# Sheet1.net
KiCad netlist of a schematic drawn in Altium Designer
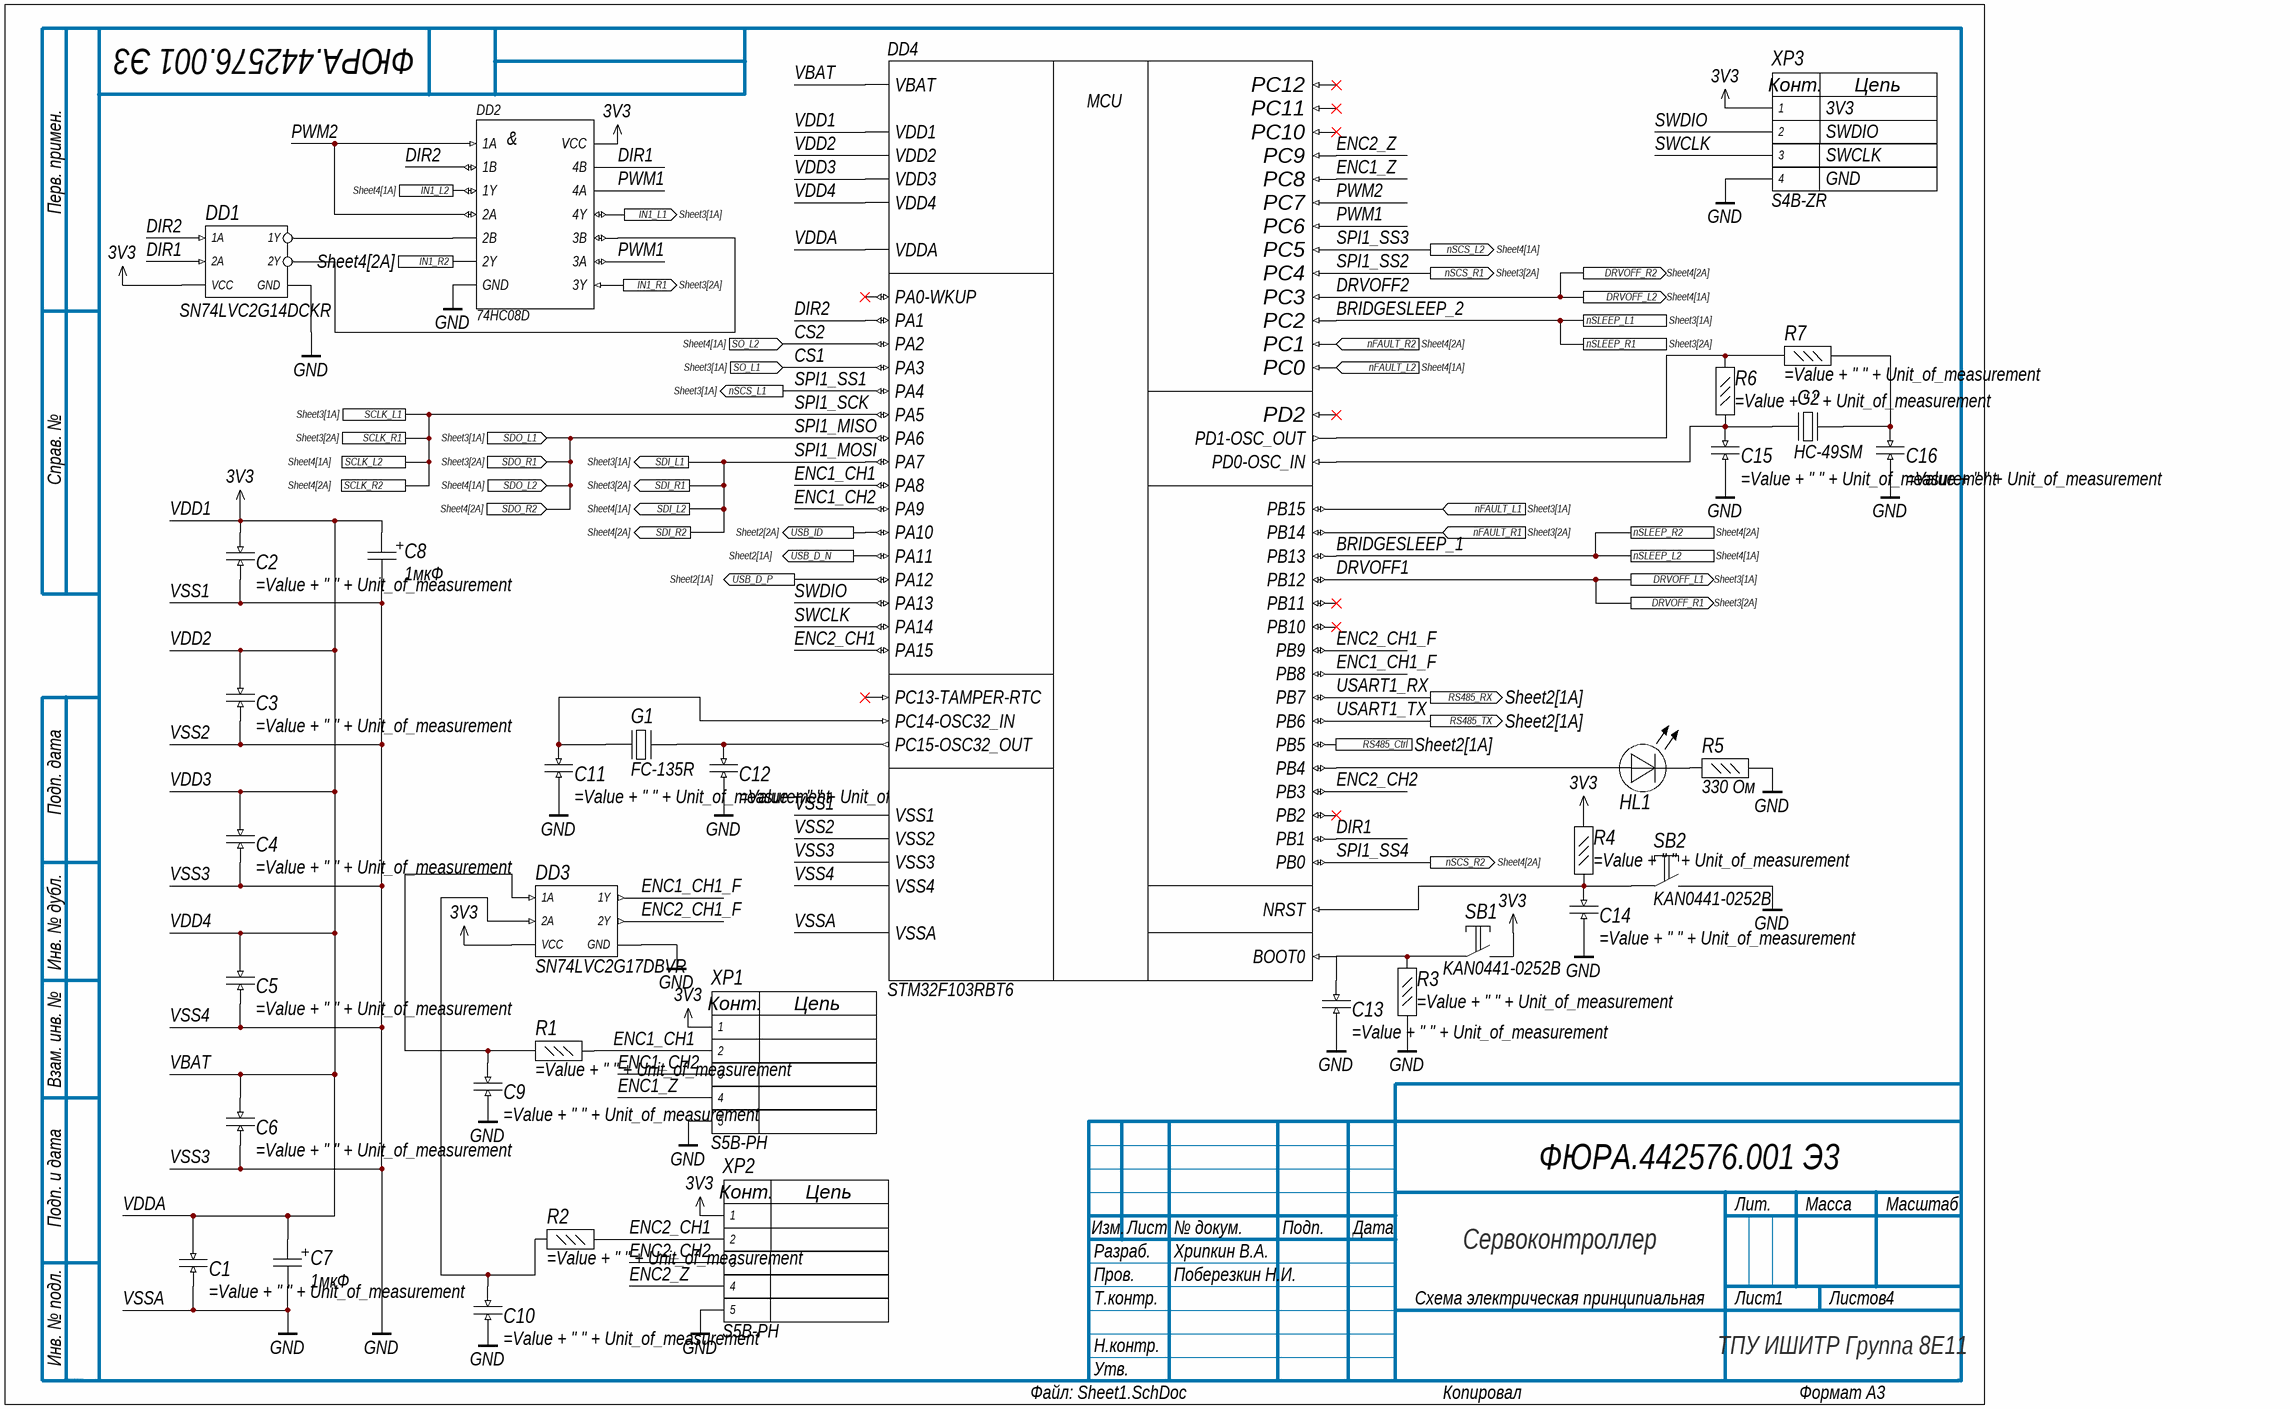
[diagram p0: Sheet1.SchDoc]

(export (version "E")
  (design (tool "Eeschema 10.0.6"))
  (components
    (comp (ref "C1")
      (value "100нФ")
      (footprint "CAP_0603")
      (description "Конденсатор керамический, типоразмера 0603")
      (libsource (lib "PassiveComponents") (part "CAP_0603"))
    )
    (comp (ref "C2")
      (value "100нФ")
      (footprint "CAP_0603")
      (description "Конденсатор керамический, типоразмера 0603")
      (libsource (lib "PassiveComponents") (part "CAP_0603"))
    )
    (comp (ref "C3")
      (value "100нФ")
      (footprint "CAP_0603")
      (description "Конденсатор керамический, типоразмера 0603")
      (libsource (lib "PassiveComponents") (part "CAP_0603"))
    )
    (comp (ref "C4")
      (value "100нФ")
      (footprint "CAP_0603")
      (description "Конденсатор керамический, типоразмера 0603")
      (libsource (lib "PassiveComponents") (part "CAP_0603"))
    )
    (comp (ref "C5")
      (value "100нФ")
      (footprint "CAP_0603")
      (description "Конденсатор керамический, типоразмера 0603")
      (libsource (lib "PassiveComponents") (part "CAP_0603"))
    )
    (comp (ref "C6")
      (value "100нФ")
      (footprint "CAP_0603")
      (description "Конденсатор керамический, типоразмера 0603")
      (libsource (lib "PassiveComponents") (part "CAP_0603"))
    )
    (comp (ref "C7")
      (value "1мкФ")
      (footprint "TECAP_A")
      (description "Описание свойств компонента")
      (libsource (lib "PassiveComponents") (part "TECAP_A"))
    )
    (comp (ref "C8")
      (value "1мкФ")
      (footprint "TECAP_A")
      (description "Описание свойств компонента")
      (libsource (lib "PassiveComponents") (part "TECAP_A"))
    )
    (comp (ref "C9")
      (value "10пФ")
      (footprint "CAP_0603")
      (description "Конденсатор керамический, типоразмера 0603")
      (libsource (lib "PassiveComponents") (part "CAP_0603"))
    )
    (comp (ref "C10")
      (value "10пФ")
      (footprint "CAP_0603")
      (description "Конденсатор керамический, типоразмера 0603")
      (libsource (lib "PassiveComponents") (part "CAP_0603"))
    )
    (comp (ref "C11")
      (value "20пФ")
      (footprint "CAP_0603")
      (description "Конденсатор керамический, типоразмера 0603")
      (libsource (lib "PassiveComponents") (part "CAP_0603"))
    )
    (comp (ref "C12")
      (value "20пФ")
      (footprint "CAP_0603")
      (description "Конденсатор керамический, типоразмера 0603")
      (libsource (lib "PassiveComponents") (part "CAP_0603"))
    )
    (comp (ref "C13")
      (value "100нФ")
      (footprint "CAP_0603")
      (description "Конденсатор керамический, типоразмера 0603")
      (libsource (lib "PassiveComponents") (part "CAP_0603"))
    )
    (comp (ref "C14")
      (value "100нФ")
      (footprint "CAP_0603")
      (description "Конденсатор керамический, типоразмера 0603")
      (libsource (lib "PassiveComponents") (part "CAP_0603"))
    )
    (comp (ref "C15")
      (value "20пФ")
      (footprint "CAP_0603")
      (description "Конденсатор керамический, типоразмера 0603")
      (libsource (lib "PassiveComponents") (part "CAP_0603"))
    )
    (comp (ref "C16")
      (value "20пФ")
      (footprint "CAP_0603")
      (description "Конденсатор керамический, типоразмера 0603")
      (libsource (lib "PassiveComponents") (part "CAP_0603"))
    )
    (comp (ref "DD1")
      (value "SN74LVC2G14DCKR")
      (footprint "SOT363 (SC70-6)")
      (description "Сдвоенный инвертор с триггером Шмидта")
      (libsource (lib "ICs") (part "SN74LVC2G14DCKR"))
    )
    (comp (ref "DD2")
      (value "74HC08D")
      (footprint "SO14")
      (description "Логическая ИС, QUAD 2-INPUT AND GATE")
      (libsource (lib "ICs") (part "74HC08D"))
    )
    (comp (ref "DD3")
      (value "SN74LVC2G17DBVR")
      (footprint "SOT23-6")
      (description "Сдвоенный буфер с триггером Шмитта на входе")
      (libsource (lib "ICs") (part "SN74LVC2G17DBVR"))
    )
    (comp (ref "DD4")
      (value "STM32F103RBT6")
      (footprint "LQFP-64")
      (description "Микроконтроллер 32-Бит, Cortex-M3, 72МГц, 128КБ Flash, USB, CAN [LQFP-64]")
      (libsource (lib "ICs") (part "STM32F103RBT6"))
    )
    (comp (ref "G1")
      (value "FC-135R")
      (footprint "FC-135R")
      (description "Кварцевый резонатор 32,768 кГц; SMD")
      (libsource (lib "Complicated") (part "FC-135R"))
    )
    (comp (ref "G2")
      (value "HC-49SM")
      (footprint "HC-49SM")
      (description "Кварцевый резонатор 8 МГц; SMD")
      (libsource (lib "Complicated") (part "HC-49SM"))
    )
    (comp (ref "HL1") (value "3") (footprint "LED_0805") (libsource (lib "Complicated") (part "LED_0805_O")))
    (comp (ref "R1")
      (value "100кОм")
      (footprint "RES_0603")
      (description "Резистор, типоразмера 0603")
      (libsource (lib "") (part "RES_0603_1"))
    )
    (comp (ref "R2")
      (value "100кОм")
      (footprint "RES_0603")
      (description "Резистор, типоразмера 0603")
      (libsource (lib "") (part "RES_0603_1"))
    )
    (comp (ref "R3")
      (value "10кОм")
      (footprint "RES_0603")
      (description "Резистор, типоразмера 0603")
      (libsource (lib "SimpleComponents") (part "RES_0603"))
    )
    (comp (ref "R4")
      (value "10кОм")
      (footprint "RES_0603")
      (description "Резистор, типоразмера 0603")
      (libsource (lib "") (part "RES_0603_2"))
    )
    (comp (ref "R5")
      (value "330 Ом")
      (footprint "RES_0603")
      (description "Резистор, типоразмера 0603")
      (libsource (lib "") (part "RES_0603_1"))
    )
    (comp (ref "R6")
      (value "1МОм")
      (footprint "RES_0603")
      (description "Резистор, типоразмера 0603")
      (libsource (lib "") (part "RES_0603_2"))
    )
    (comp (ref "R7")
      (value "100кОм")
      (footprint "RES_0603")
      (description "Резистор, типоразмера 0603")
      (libsource (lib "") (part "RES_0603_1"))
    )
    (comp (ref "SB1")
      (value "KAN0441-0252B")
      (footprint "SMD-BUTTON_6x3.5")
      (description "Описание свойств компонента")
      (libsource (lib "PassiveComponents") (part "SMD-Button_6x3.5"))
    )
    (comp (ref "SB2")
      (value "KAN0441-0252B")
      (footprint "SMD-BUTTON_6x3.5")
      (description "Описание свойств компонента")
      (libsource (lib "PassiveComponents") (part "SMD-Button_6x3.5"))
    )
    (comp (ref "XP1")
      (value "S5B-PH")
      (footprint "S5B-PH-K-S")
      (description "JST PH 5pin 2 mm pitch; horizontal; through hole OR full smd; S5B-PH-SM4-TB")
      (libsource (lib "SimpleComponents") (part "S5B-PH"))
    )
    (comp (ref "XP2")
      (value "S5B-PH")
      (footprint "S5B-PH-K-S")
      (description "JST PH 5pin 2 mm pitch; horizontal; through hole OR full smd; S5B-PH-SM4-TB")
      (libsource (lib "SimpleComponents") (part "S5B-PH"))
    )
    (comp (ref "XP3")
      (value "S4B-ZR")
      (footprint "S4B-ZR-SM4A-TF")
      (description "JST ZH 4pin 1.5 mm pitch; horizontal; through hole OR full smd; S4B-ZR")
      (libsource (lib "PassiveComponents") (part "S4B-ZR"))
    )
  )
  (nets
    (net (code "1") (name "/BRIDGESLEEP_1") (class "Default")
      (node (ref "DD4") (pin "34") (pinfunction "PB13_34") (pintype "bidirectional"))
    )
    (net (code "2") (name "/BRIDGESLEEP_2") (class "Default")
      (node (ref "DD4") (pin "10") (pinfunction "PC2_10") (pintype "input"))
    )
    (net (code "3") (name "/CS1") (class "Default")
      (node (ref "DD4") (pin "17") (pinfunction "PA3_17") (pintype "bidirectional"))
    )
    (net (code "4") (name "/CS2") (class "Default")
      (node (ref "DD4") (pin "16") (pinfunction "PA2_16") (pintype "bidirectional"))
    )
    (net (code "5") (name "/DIR1") (class "Default")
      (node (ref "DD1") (pin "3") (pinfunction "2A_3") (pintype "input"))
      (node (ref "DD2") (pin "13") (pinfunction "4B_13") (pintype "power_in"))
      (node (ref "DD4") (pin "27") (pinfunction "PB1_27") (pintype "bidirectional"))
    )
    (net (code "6") (name "/DIR2") (class "Default")
      (node (ref "DD1") (pin "1") (pinfunction "1A_1") (pintype "input"))
      (node (ref "DD2") (pin "2") (pinfunction "1B_2") (pintype "bidirectional"))
      (node (ref "DD4") (pin "15") (pinfunction "PA1_15") (pintype "bidirectional"))
    )
    (net (code "7") (name "/DRVOFF1") (class "Default")
      (node (ref "DD4") (pin "33") (pinfunction "PB12_33") (pintype "bidirectional"))
    )
    (net (code "8") (name "/DRVOFF2") (class "Default")
      (node (ref "DD4") (pin "11") (pinfunction "PC3_11") (pintype "input"))
    )
    (net (code "9") (name "/ENC1_CH1") (class "Default")
      (node (ref "DD4") (pin "41") (pinfunction "PA8_41") (pintype "bidirectional"))
      (node (ref "R1") (pin "2") (pinfunction "2_2") (pintype "passive"))
      (node (ref "XP1") (pin "2") (pinfunction "2_2") (pintype "passive"))
    )
    (net (code "10") (name "/ENC1_CH1_F") (class "Default")
      (node (ref "DD3") (pin "6") (pinfunction "1Y_6") (pintype "output"))
      (node (ref "DD4") (pin "61") (pinfunction "PB8_61") (pintype "bidirectional"))
    )
    (net (code "11") (name "/ENC1_CH2") (class "Default")
      (node (ref "DD4") (pin "42") (pinfunction "PA9_42") (pintype "bidirectional"))
      (node (ref "XP1") (pin "3") (pinfunction "3_3") (pintype "passive"))
    )
    (net (code "12") (name "/ENC1_Z") (class "Default")
      (node (ref "DD4") (pin "39") (pinfunction "PC8_39") (pintype "input"))
      (node (ref "XP1") (pin "4") (pinfunction "4_4") (pintype "passive"))
    )
    (net (code "13") (name "/ENC2_CH1") (class "Default")
      (node (ref "DD4") (pin "50") (pinfunction "PA15_50") (pintype "bidirectional"))
      (node (ref "R2") (pin "2") (pinfunction "2_2") (pintype "passive"))
      (node (ref "XP2") (pin "2") (pinfunction "2_2") (pintype "passive"))
    )
    (net (code "14") (name "/ENC2_CH1_F") (class "Default")
      (node (ref "DD3") (pin "4") (pinfunction "2Y_4") (pintype "output"))
      (node (ref "DD4") (pin "62") (pinfunction "PB9_62") (pintype "bidirectional"))
    )
    (net (code "15") (name "/ENC2_CH2") (class "Default")
      (node (ref "DD4") (pin "55") (pinfunction "PB3_55") (pintype "bidirectional"))
      (node (ref "XP2") (pin "3") (pinfunction "3_3") (pintype "passive"))
    )
    (net (code "16") (name "/ENC2_Z") (class "Default")
      (node (ref "DD4") (pin "40") (pinfunction "PC9_40") (pintype "input"))
      (node (ref "XP2") (pin "4") (pinfunction "4_4") (pintype "passive"))
    )
    (net (code "17") (name "/IN1_L1") (class "Default")
      (node (ref "DD2") (pin "11") (pinfunction "4Y_11") (pintype "bidirectional"))
    )
    (net (code "18") (name "/IN1_L2") (class "Default")
      (node (ref "DD2") (pin "3") (pinfunction "1Y_3") (pintype "bidirectional"))
    )
    (net (code "19") (name "/IN1_R1") (class "Default")
      (node (ref "DD2") (pin "8") (pinfunction "3Y_8") (pintype "input"))
    )
    (net (code "20") (name "/IN1_R2") (class "Default")
      (node (ref "DD2") (pin "6") (pinfunction "2Y_6") (pintype "power_in"))
    )
    (net (code "21") (name "/PWM1") (class "Default")
      (node (ref "DD2") (pin "12") (pinfunction "4A_12") (pintype "power_in"))
      (node (ref "DD2") (pin "9") (pinfunction "3A_9") (pintype "bidirectional"))
      (node (ref "DD4") (pin "37") (pinfunction "PC6_37") (pintype "input"))
    )
    (net (code "22") (name "/PWM2") (class "Default")
      (node (ref "DD2") (pin "1") (pinfunction "1A_1") (pintype "input"))
      (node (ref "DD2") (pin "4") (pinfunction "2A_4") (pintype "bidirectional"))
      (node (ref "DD4") (pin "38") (pinfunction "PC7_38") (pintype "input"))
    )
    (net (code "23") (name "/RS485_Ctrl") (class "Default")
      (node (ref "DD4") (pin "57") (pinfunction "PB5_57") (pintype "bidirectional"))
    )
    (net (code "24") (name "/SPI1_MISO") (class "Default")
      (node (ref "DD4") (pin "22") (pinfunction "PA6_22") (pintype "bidirectional"))
    )
    (net (code "25") (name "/SPI1_MOSI") (class "Default")
      (node (ref "DD4") (pin "23") (pinfunction "PA7_23") (pintype "bidirectional"))
    )
    (net (code "26") (name "/SPI1_SCK") (class "Default")
      (node (ref "DD4") (pin "21") (pinfunction "PA5_21") (pintype "bidirectional"))
    )
    (net (code "27") (name "/SPI1_SS1") (class "Default")
      (node (ref "DD4") (pin "20") (pinfunction "PA4_20") (pintype "bidirectional"))
    )
    (net (code "28") (name "/SPI1_SS2") (class "Default")
      (node (ref "DD4") (pin "24") (pinfunction "PC4_24") (pintype "input"))
    )
    (net (code "29") (name "/SPI1_SS3") (class "Default")
      (node (ref "DD4") (pin "25") (pinfunction "PC5_25") (pintype "input"))
    )
    (net (code "30") (name "/SPI1_SS4") (class "Default")
      (node (ref "DD4") (pin "26") (pinfunction "PB0_26") (pintype "bidirectional"))
    )
    (net (code "31") (name "/SWCLK") (class "Default")
      (node (ref "DD4") (pin "49") (pinfunction "PA14_49") (pintype "bidirectional"))
      (node (ref "XP3") (pin "3") (pinfunction "3_3") (pintype "passive"))
    )
    (net (code "32") (name "/SWDIO") (class "Default")
      (node (ref "DD4") (pin "46") (pinfunction "PA13_46") (pintype "bidirectional"))
      (node (ref "XP3") (pin "2") (pinfunction "2_2") (pintype "passive"))
    )
    (net (code "33") (name "/USART1_RX") (class "Default")
      (node (ref "DD4") (pin "59") (pinfunction "PB7_59") (pintype "bidirectional"))
    )
    (net (code "34") (name "/USART1_TX") (class "Default")
      (node (ref "DD4") (pin "58") (pinfunction "PB6_58") (pintype "bidirectional"))
    )
    (net (code "35") (name "/USB_D_N") (class "Default")
      (node (ref "DD4") (pin "44") (pinfunction "PA11_44") (pintype "bidirectional"))
    )
    (net (code "36") (name "/USB_D_P") (class "Default")
      (node (ref "DD4") (pin "45") (pinfunction "PA12_45") (pintype "bidirectional"))
    )
    (net (code "37") (name "/USB_ID") (class "Default")
      (node (ref "DD4") (pin "43") (pinfunction "PA10_43") (pintype "bidirectional"))
    )
    (net (code "38") (name "/nFAULT_L1") (class "Default")
      (node (ref "DD4") (pin "36") (pinfunction "PB15_36") (pintype "bidirectional"))
    )
    (net (code "39") (name "/nFAULT_L2") (class "Default")
      (node (ref "DD4") (pin "8") (pinfunction "PC0_8") (pintype "input"))
    )
    (net (code "40") (name "/nFAULT_R1") (class "Default")
      (node (ref "DD4") (pin "35") (pinfunction "PB14_35") (pintype "bidirectional"))
    )
    (net (code "41") (name "/nFAULT_R2") (class "Default")
      (node (ref "DD4") (pin "9") (pinfunction "PC1_9") (pintype "input"))
    )
    (net (code "42") (name "3V3") (class "Default")
      (node (ref "C1") (pin "2") (pintype "input"))
      (node (ref "C2") (pin "2") (pintype "input"))
      (node (ref "C3") (pin "2") (pintype "input"))
      (node (ref "C4") (pin "2") (pintype "input"))
      (node (ref "C5") (pin "2") (pintype "input"))
      (node (ref "C6") (pin "2") (pintype "input"))
      (node (ref "C7") (pin "1") (pintype "passive"))
      (node (ref "C8") (pin "1") (pintype "passive"))
      (node (ref "DD1") (pin "5") (pinfunction "VCC_5") (pintype "power_in"))
      (node (ref "DD2") (pin "14") (pinfunction "VCC_14") (pintype "power_in"))
      (node (ref "DD3") (pin "5") (pinfunction "VCC_5") (pintype "power_in"))
      (node (ref "DD4") (pin "1") (pinfunction "VBAT_1") (pintype "power_in"))
      (node (ref "DD4") (pin "13") (pinfunction "VDDA_13") (pintype "power_in"))
      (node (ref "DD4") (pin "19") (pinfunction "VDD1_19") (pintype "power_in"))
      (node (ref "DD4") (pin "32") (pinfunction "VDD2_32") (pintype "power_in"))
      (node (ref "DD4") (pin "48") (pinfunction "VDD3_48") (pintype "power_in"))
      (node (ref "DD4") (pin "64") (pinfunction "VDD4_64") (pintype "power_in"))
      (node (ref "R4") (pin "2") (pinfunction "2_2") (pintype "passive"))
      (node (ref "SB1") (pin "2") (pinfunction "S2_2") (pintype "passive"))
      (node (ref "XP1") (pin "1") (pinfunction "1_1") (pintype "passive"))
      (node (ref "XP2") (pin "1") (pinfunction "1_1") (pintype "passive"))
      (node (ref "XP3") (pin "1") (pinfunction "1_1") (pintype "passive"))
    )
    (net (code "43") (name "GND") (class "Default")
      (node (ref "C1") (pin "1") (pintype "input"))
      (node (ref "C10") (pin "1") (pintype "input"))
      (node (ref "C11") (pin "1") (pintype "input"))
      (node (ref "C12") (pin "1") (pintype "input"))
      (node (ref "C13") (pin "1") (pintype "input"))
      (node (ref "C14") (pin "1") (pintype "input"))
      (node (ref "C15") (pin "1") (pintype "input"))
      (node (ref "C16") (pin "1") (pintype "input"))
      (node (ref "C2") (pin "1") (pintype "input"))
      (node (ref "C3") (pin "1") (pintype "input"))
      (node (ref "C4") (pin "1") (pintype "input"))
      (node (ref "C5") (pin "1") (pintype "input"))
      (node (ref "C6") (pin "1") (pintype "input"))
      (node (ref "C7") (pin "2") (pintype "passive"))
      (node (ref "C8") (pin "2") (pintype "passive"))
      (node (ref "C9") (pin "1") (pintype "input"))
      (node (ref "DD1") (pin "2") (pinfunction "GND_2") (pintype "power_in"))
      (node (ref "DD2") (pin "7") (pinfunction "GND_7") (pintype "power_in"))
      (node (ref "DD3") (pin "2") (pinfunction "GND_2") (pintype "power_in"))
      (node (ref "DD4") (pin "12") (pinfunction "VSSA_12") (pintype "power_in"))
      (node (ref "DD4") (pin "18") (pinfunction "VSS1_18") (pintype "power_in"))
      (node (ref "DD4") (pin "31") (pinfunction "VSS2_31") (pintype "power_in"))
      (node (ref "DD4") (pin "47") (pinfunction "VSS3_47") (pintype "power_in"))
      (node (ref "DD4") (pin "63") (pinfunction "VSS4_63") (pintype "power_in"))
      (node (ref "R3") (pin "2") (pinfunction "2_2") (pintype "passive"))
      (node (ref "R5") (pin "2") (pinfunction "2_2") (pintype "passive"))
      (node (ref "SB2") (pin "2") (pinfunction "S2_2") (pintype "passive"))
      (node (ref "XP1") (pin "5") (pinfunction "5_5") (pintype "passive"))
      (node (ref "XP2") (pin "5") (pinfunction "5_5") (pintype "passive"))
      (node (ref "XP3") (pin "4") (pinfunction "4_4") (pintype "passive"))
    )
    (net (code "44") (name "Net-(C16-Pad2)") (class "Default")
      (node (ref "C16") (pin "2") (pintype "input"))
      (node (ref "G2") (pin "2") (pintype "passive"))
      (node (ref "R7") (pin "2") (pinfunction "2_2") (pintype "passive"))
    )
    (net (code "45") (name "Net-(DD1-1Y)") (class "Default")
      (node (ref "DD1") (pin "6") (pinfunction "1Y_6") (pintype "output"))
      (node (ref "DD2") (pin "5") (pinfunction "2B_5") (pintype "power_in"))
    )
    (net (code "46") (name "Net-(DD1-2Y)") (class "Default")
      (node (ref "DD1") (pin "4") (pinfunction "2Y_4") (pintype "output"))
      (node (ref "DD2") (pin "10") (pinfunction "3B_10") (pintype "bidirectional"))
    )
    (net (code "47") (name "Net-(DD3-1A)") (class "Default")
      (node (ref "C9") (pin "2") (pintype "input"))
      (node (ref "DD3") (pin "1") (pinfunction "1A_1") (pintype "input"))
      (node (ref "R1") (pin "1") (pinfunction "1_1") (pintype "passive"))
    )
    (net (code "48") (name "Net-(DD3-2A)") (class "Default")
      (node (ref "C10") (pin "2") (pintype "input"))
      (node (ref "DD3") (pin "3") (pinfunction "2A_3") (pintype "input"))
      (node (ref "R2") (pin "1") (pinfunction "1_1") (pintype "passive"))
    )
    (net (code "49") (name "Net-(DD4-BOOT0)") (class "Default")
      (node (ref "C13") (pin "2") (pintype "input"))
      (node (ref "DD4") (pin "60") (pinfunction "BOOT0_60") (pintype "input"))
      (node (ref "R3") (pin "1") (pinfunction "1_1") (pintype "passive"))
      (node (ref "SB1") (pin "1") (pinfunction "S1_1") (pintype "passive"))
    )
    (net (code "50") (name "Net-(DD4-NRST)") (class "Default")
      (node (ref "C14") (pin "2") (pintype "input"))
      (node (ref "DD4") (pin "7") (pinfunction "NRST_7") (pintype "input"))
      (node (ref "R4") (pin "1") (pinfunction "1_1") (pintype "passive"))
      (node (ref "SB2") (pin "1") (pinfunction "S1_1") (pintype "passive"))
    )
    (net (code "51") (name "Net-(DD4-PB4)") (class "Default")
      (node (ref "DD4") (pin "56") (pinfunction "PB4_56") (pintype "bidirectional"))
      (node (ref "HL1") (pin "A") (pinfunction "2_A") (pintype "passive"))
    )
    (net (code "52") (name "Net-(DD4-PC14-OSC32_IN)") (class "Default")
      (node (ref "C11") (pin "2") (pintype "input"))
      (node (ref "DD4") (pin "3") (pinfunction "PC14-OSC32_IN_3") (pintype "input"))
      (node (ref "G1") (pin "1") (pintype "passive"))
    )
    (net (code "53") (name "Net-(DD4-PC15-OSC32_OUT)") (class "Default")
      (node (ref "C12") (pin "2") (pintype "input"))
      (node (ref "DD4") (pin "4") (pinfunction "PC15-OSC32_OUT_4") (pintype "output"))
      (node (ref "G1") (pin "2") (pintype "passive"))
    )
    (net (code "54") (name "Net-(DD4-PD0-OSC_IN)") (class "Default")
      (node (ref "C15") (pin "2") (pintype "input"))
      (node (ref "DD4") (pin "5") (pinfunction "PD0-OSC_IN_5") (pintype "input"))
      (node (ref "G2") (pin "1") (pintype "passive"))
      (node (ref "R6") (pin "1") (pinfunction "1_1") (pintype "passive"))
    )
    (net (code "55") (name "Net-(DD4-PD1-OSC_OUT)") (class "Default")
      (node (ref "DD4") (pin "6") (pinfunction "PD1-OSC_OUT_6") (pintype "output"))
      (node (ref "R6") (pin "2") (pinfunction "2_2") (pintype "passive"))
      (node (ref "R7") (pin "1") (pinfunction "1_1") (pintype "passive"))
    )
    (net (code "56") (name "Net-(HL1-1)") (class "Default")
      (node (ref "HL1") (pin "C") (pinfunction "1_C") (pintype "passive"))
      (node (ref "R5") (pin "1") (pinfunction "1_1") (pintype "passive"))
    )
    (net (code "57") (name "unconnected-(DD4-PA0-WKUP-Pad14)") (class "Default")
      (node (ref "DD4") (pin "14") (pinfunction "PA0-WKUP_14") (pintype "bidirectional+no_connect"))
    )
    (net (code "58") (name "unconnected-(DD4-PB2-Pad28)") (class "Default")
      (node (ref "DD4") (pin "28") (pinfunction "PB2_28") (pintype "bidirectional+no_connect"))
    )
    (net (code "59") (name "unconnected-(DD4-PB10-Pad29)") (class "Default")
      (node (ref "DD4") (pin "29") (pinfunction "PB10_29") (pintype "bidirectional+no_connect"))
    )
    (net (code "60") (name "unconnected-(DD4-PB11-Pad30)") (class "Default")
      (node (ref "DD4") (pin "30") (pinfunction "PB11_30") (pintype "bidirectional+no_connect"))
    )
    (net (code "61") (name "unconnected-(DD4-PC10-Pad51)") (class "Default")
      (node (ref "DD4") (pin "51") (pinfunction "PC10_51") (pintype "input+no_connect"))
    )
    (net (code "62") (name "unconnected-(DD4-PC11-Pad52)") (class "Default")
      (node (ref "DD4") (pin "52") (pinfunction "PC11_52") (pintype "input+no_connect"))
    )
    (net (code "63") (name "unconnected-(DD4-PC12-Pad53)") (class "Default")
      (node (ref "DD4") (pin "53") (pinfunction "PC12_53") (pintype "input+no_connect"))
    )
    (net (code "64") (name "unconnected-(DD4-PC13-TAMPER-RTC-Pad2)") (class "Default")
      (node (ref "DD4") (pin "2") (pinfunction "PC13-TAMPER-RTC_2") (pintype "input+no_connect"))
    )
    (net (code "65") (name "unconnected-(DD4-PD2-Pad54)") (class "Default")
      (node (ref "DD4") (pin "54") (pinfunction "PD2_54") (pintype "input+no_connect"))
    )
  )
)
